# H-bridge.net
KiCad netlist of a schematic drawn in Altium Designer
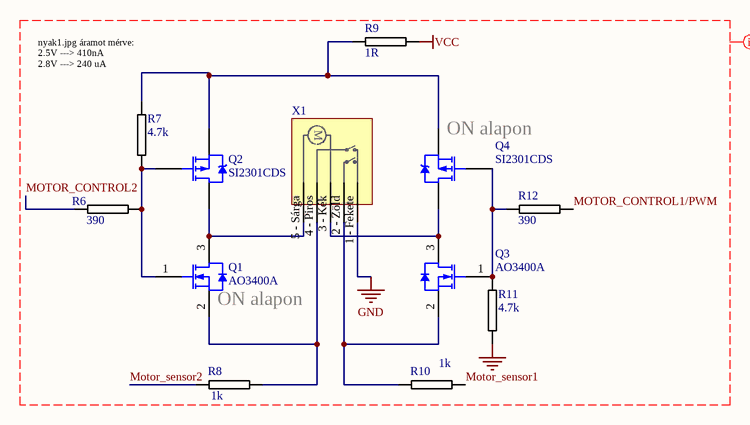
[diagram p0: H-bridge.SchDoc]

(export (version "E")
  (design (tool "Eeschema 10.0.6"))
  (components
    (comp (ref "Q1")
      (value "AO3400A")
      (footprint "INF-PG-SOT23_N")
      (fields (field (name "MANUFACTURER") "Infineon") (field (name "PARTNUMBER") "IRLML6244"))
      (libsource (lib "Infineon_Power_MOSFET") (part "BSS806N"))
    )
    (comp (ref "Q2")
      (value "SI2301CDS")
      (footprint "Micro3_N")
      (description "HEXFET Power MOSFET")
      (fields (field (name "PUBLISHER") "Altium Limited"))
      (libsource (lib "IR Discrete MOSFET - Power") (part "IRLML6401"))
    )
    (comp (ref "Q3")
      (value "AO3400A")
      (footprint "INF-PG-SOT23_N")
      (fields (field (name "MANUFACTURER") "Infineon") (field (name "PARTNUMBER") "BSS806N"))
      (libsource (lib "Infineon_Power_MOSFET") (part "BSS806N"))
    )
    (comp (ref "Q4")
      (value "SI2301CDS")
      (footprint "Micro3_N")
      (description "HEXFET Power MOSFET")
      (fields (field (name "PUBLISHER") "Altium Limited"))
      (libsource (lib "IR Discrete MOSFET - Power") (part "IRLML6401"))
    )
    (comp (ref "R6")
      (value "390")
      (footprint "0805R-390")
      (description "RESISTOR 0805 1/4 WATT THIN FILM")
      (libsource (lib "vh_altium_library") (part "0805R-390"))
    )
    (comp (ref "R7")
      (value "4.7k")
      (footprint "0805R-10K")
      (description "RESISTOR 0805 1/4 WATT THIN FILM")
      (libsource (lib "vh_altium_library") (part "0805R-10K"))
    )
    (comp (ref "R8")
      (value "1k")
      (footprint "0805R-1K")
      (description "RESISTOR 0805 1/4 WATT THIN FILM")
      (libsource (lib "vh_altium_library") (part "0805R-1K"))
    )
    (comp (ref "R9")
      (value "1R")
      (footprint "1206FB-50Z")
      (description "RESISTOR 0805 1/3 WATT")
      (libsource (lib "vh_altium_library") (part "0805R-1R"))
    )
    (comp (ref "R10")
      (value "1k")
      (footprint "0805R-1K")
      (description "RESISTOR 0805 1/4 WATT THIN FILM")
      (libsource (lib "vh_altium_library") (part "0805R-1K"))
    )
    (comp (ref "R11")
      (value "4.7k")
      (footprint "0805R-10K")
      (description "RESISTOR 0805 1/4 WATT THIN FILM")
      (libsource (lib "vh_altium_library") (part "0805R-10K"))
    )
    (comp (ref "R12")
      (value "390")
      (footprint "0805R-390")
      (description "RESISTOR 0805 1/4 WATT THIN FILM")
      (libsource (lib "vh_altium_library") (part "0805R-390"))
    )
    (comp (ref "X1")
      (value "Component_1")
      (footprint "Szelep_csati")
      (libsource (lib "components") (part "szelep_csati1"))
    )
  )
  (nets
    (net (code "1") (name "/MOTOR_CONTROL1{slash}PWM") (class "Default")
      (node (ref "R12") (pin "2") (pintype "passive"))
    )
    (net (code "2") (name "/MOTOR_CONTROL2") (class "Default")
      (node (ref "R6") (pin "1") (pintype "passive"))
    )
    (net (code "3") (name "/Motor_sensor1") (class "Default")
      (node (ref "R10") (pin "2") (pintype "passive"))
    )
    (net (code "4") (name "/Motor_sensor2") (class "Default") (node (ref "R8") (pin "1") (pintype "passive")))
    (net (code "5") (name "GND") (class "Default")
      (node (ref "R11") (pin "2") (pintype "passive"))
      (node (ref "X1") (pin "1_-_Fekete") (pinfunction "1_1_-_Fekete") (pintype "passive"))
    )
    (net (code "6") (name "Net-(Q1-DRAIN)") (class "Default")
      (node (ref "Q1") (pin "3") (pinfunction "DRAIN_3") (pintype "passive"))
      (node (ref "Q2") (pin "3") (pinfunction "D_3") (pintype "passive"))
      (node (ref "X1") (pin "5_-_Sárga") (pinfunction "5_5_-_Sárga") (pintype "passive"))
    )
    (net (code "7") (name "Net-(Q1-GATE)") (class "Default")
      (node (ref "Q1") (pin "1") (pinfunction "GATE_1") (pintype "passive"))
      (node (ref "Q2") (pin "1") (pinfunction "G_1") (pintype "passive"))
      (node (ref "R6") (pin "2") (pintype "passive"))
      (node (ref "R7") (pin "2") (pintype "passive"))
    )
    (net (code "8") (name "Net-(Q1-SOURCE)") (class "Default")
      (node (ref "Q1") (pin "2") (pinfunction "SOURCE_2") (pintype "passive"))
      (node (ref "R8") (pin "2") (pintype "passive"))
      (node (ref "X1") (pin "4_-_Piros") (pinfunction "4_4_-_Piros") (pintype "passive"))
    )
    (net (code "9") (name "Net-(Q2-S)") (class "Default")
      (node (ref "Q2") (pin "2") (pinfunction "S_2") (pintype "passive"))
      (node (ref "Q4") (pin "2") (pinfunction "S_2") (pintype "passive"))
      (node (ref "R7") (pin "1") (pintype "passive"))
      (node (ref "R9") (pin "1") (pintype "passive"))
    )
    (net (code "10") (name "Net-(Q3-DRAIN)") (class "Default")
      (node (ref "Q3") (pin "3") (pinfunction "DRAIN_3") (pintype "passive"))
      (node (ref "Q4") (pin "3") (pinfunction "D_3") (pintype "passive"))
      (node (ref "X1") (pin "3_-_Kék") (pinfunction "3_3_-_Kék") (pintype "passive"))
    )
    (net (code "11") (name "Net-(Q3-GATE)") (class "Default")
      (node (ref "Q3") (pin "1") (pinfunction "GATE_1") (pintype "passive"))
      (node (ref "Q4") (pin "1") (pinfunction "G_1") (pintype "passive"))
      (node (ref "R11") (pin "1") (pintype "passive"))
      (node (ref "R12") (pin "1") (pintype "passive"))
    )
    (net (code "12") (name "Net-(Q3-SOURCE)") (class "Default")
      (node (ref "Q3") (pin "2") (pinfunction "SOURCE_2") (pintype "passive"))
      (node (ref "R10") (pin "1") (pintype "passive"))
      (node (ref "X1") (pin "2_-_Zöld") (pinfunction "2_2_-_Zöld") (pintype "passive"))
    )
    (net (code "13") (name "VCC") (class "Default") (node (ref "R9") (pin "2") (pintype "passive")))
  )
)
